# EvoProject_2_0.net
KiCad netlist of a schematic drawn in Altium Designer
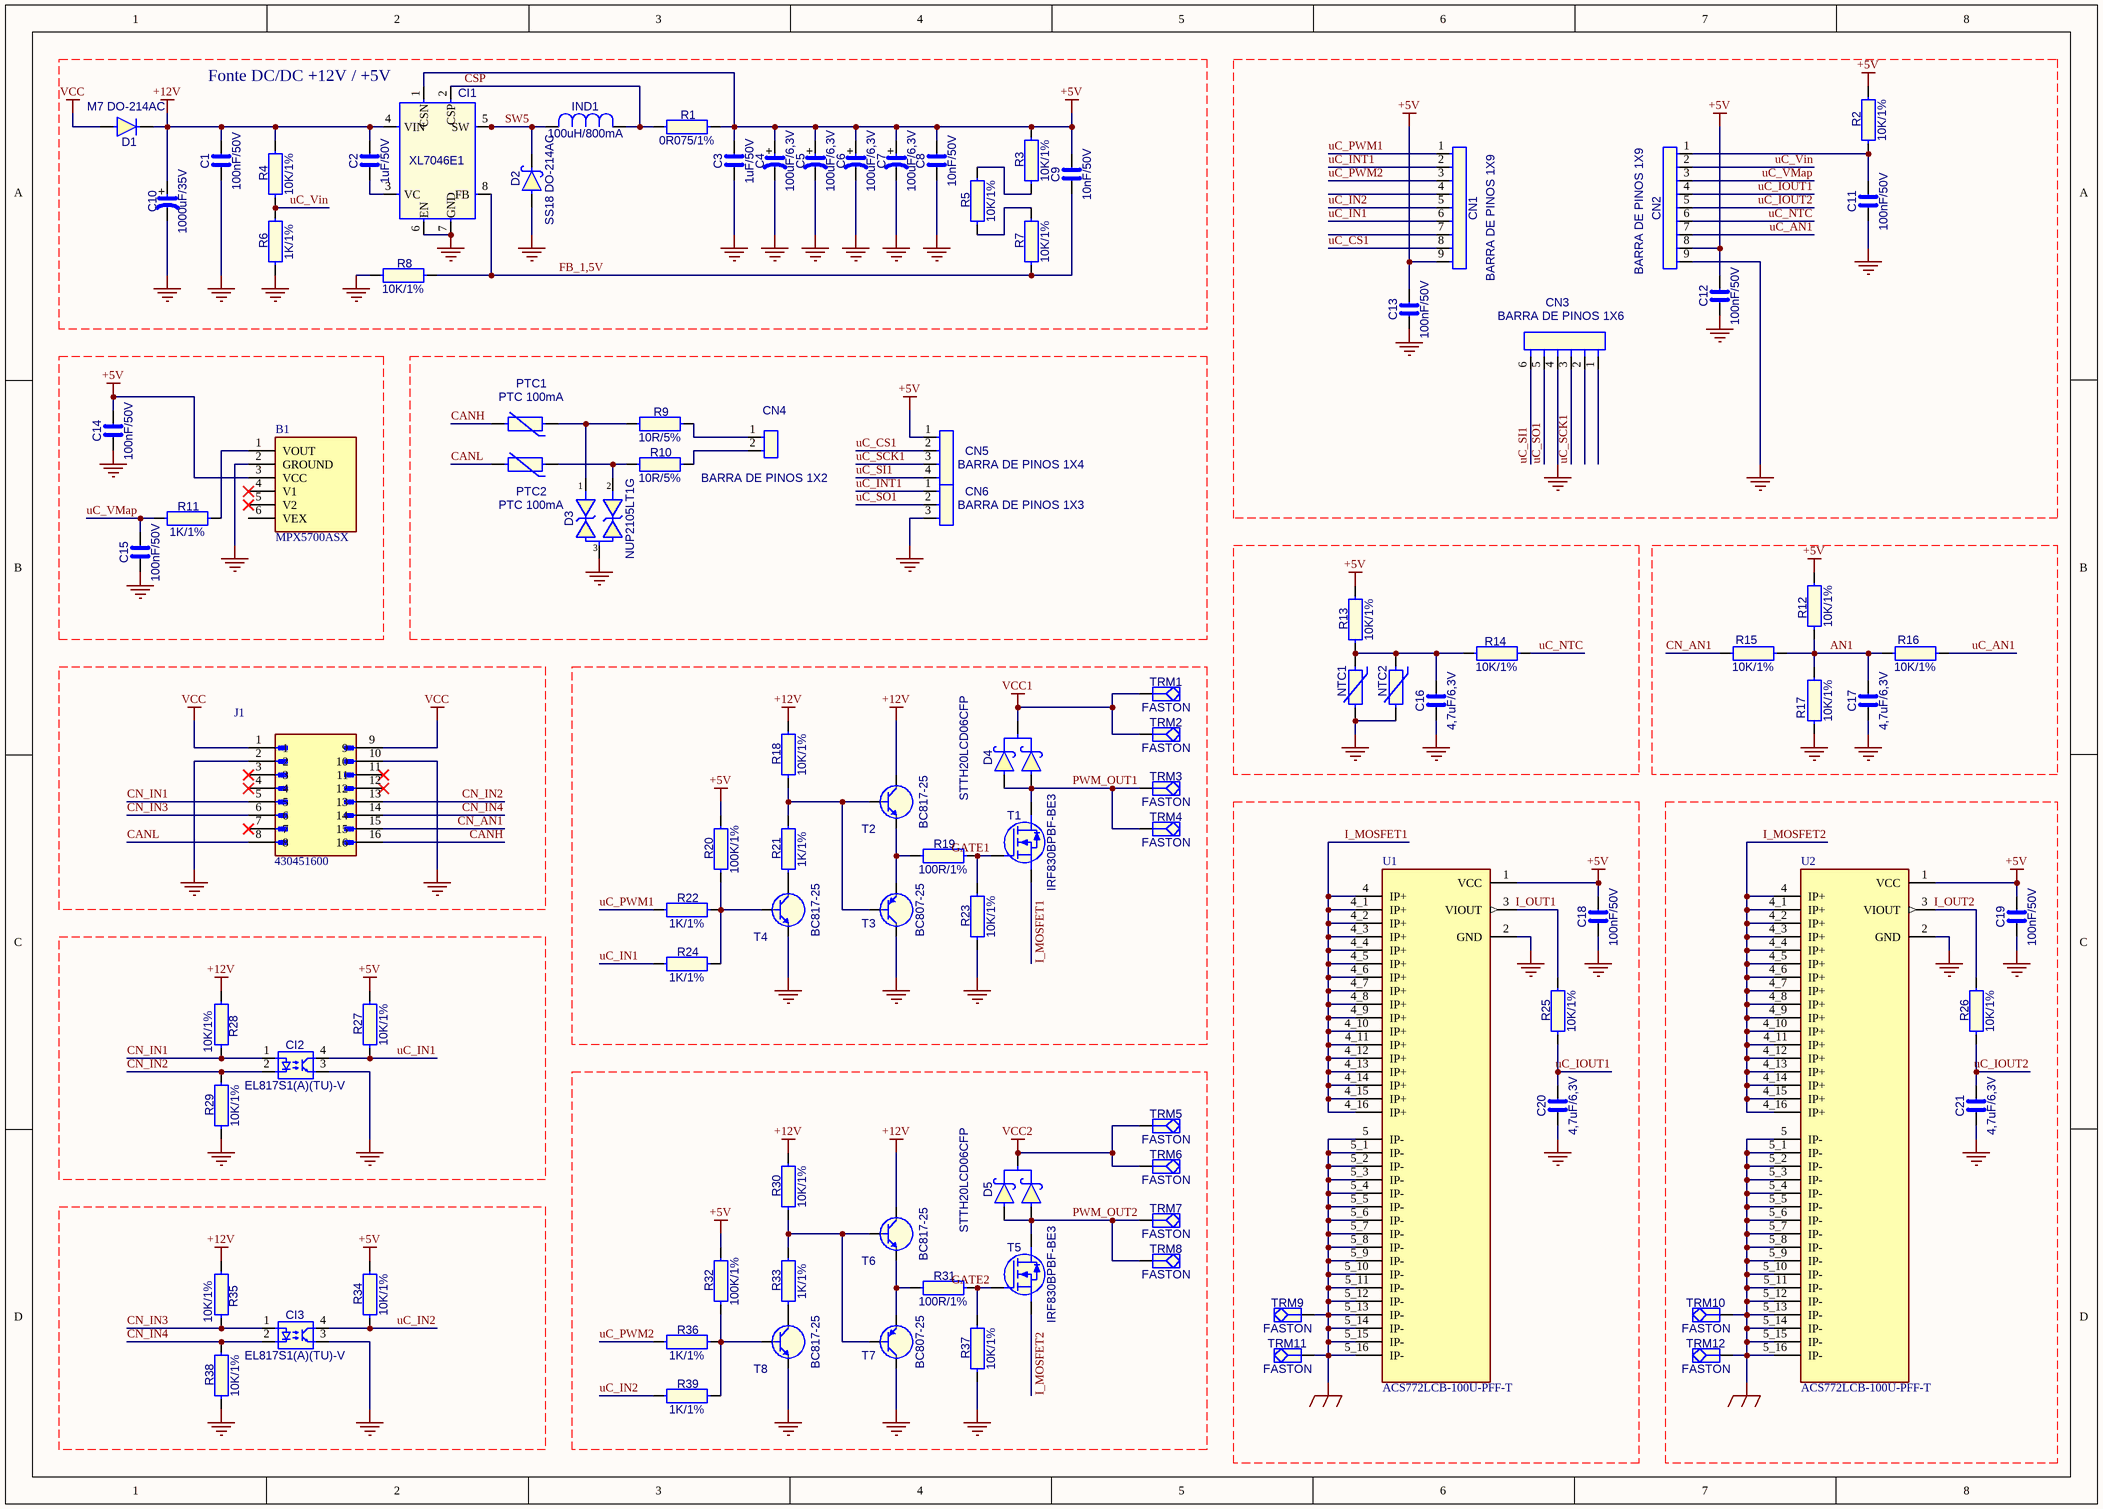
[diagram p0: EvoProject 2.0.SchDoc]

(export (version "E")
  (design (tool "Eeschema 10.0.6"))
  (components
    (comp (ref "B1")
      (value "MPX5700ASX")
      (footprint "MPX5700ASX")
      (libsource (lib "Inova_2015") (part "MPX5700ASX"))
    )
    (comp (ref "C1")
      (value "100nF/50V")
      (footprint "CAP SMD CE 0603 HR")
      (description "CAPACITOR SMD CE 0603 100nF 50V 10% X7R")
      (libsource (lib "INOVA SISTEMAS ELETRONICOS") (part "CAP_NP"))
    )
    (comp (ref "C2")
      (value "1uF/50V")
      (footprint "CAP SMD CE 0603 HR")
      (description "CAPACITOR SMD CE 0603 1uF 50V 10% X5R")
      (libsource (lib "INOVA SISTEMAS ELETRONICOS") (part "CAP_NP"))
    )
    (comp (ref "C3")
      (value "1uF/50V")
      (footprint "CAP SMD CE 0603 HR")
      (description "CAPACITOR SMD CE 0603 1uF 50V 10% X5R")
      (libsource (lib "INOVA SISTEMAS ELETRONICOS") (part "CAP_NP"))
    )
    (comp (ref "C4")
      (value "100uF/6,3V")
      (footprint "CAP SMD EL D.6,30 H.5,40 P.4,80 HR")
      (description "CAPACITOR SMD EL D.6.3 H.5.4mm 100uF 6.3V 20% BESR")
      (libsource (lib "INOVA SISTEMAS ELETRONICOS") (part "CAP_P"))
    )
    (comp (ref "C5")
      (value "100uF/6,3V")
      (footprint "CAP SMD EL D.6,30 H.5,40 P.4,80 HR")
      (description "CAPACITOR SMD EL D.6.3 H.5.4mm 100uF 6.3V 20% BESR")
      (libsource (lib "INOVA SISTEMAS ELETRONICOS") (part "CAP_P"))
    )
    (comp (ref "C6")
      (value "100uF/6,3V")
      (footprint "CAP SMD EL D.6,30 H.5,40 P.4,80 HR")
      (description "CAPACITOR SMD EL D.6.3 H.5.4mm 100uF 6.3V 20% BESR")
      (libsource (lib "INOVA SISTEMAS ELETRONICOS") (part "CAP_P"))
    )
    (comp (ref "C7")
      (value "100uF/6,3V")
      (footprint "CAP SMD EL D.6,30 H.5,40 P.4,80 HR")
      (description "CAPACITOR SMD EL D.6.3 H.5.4mm 100uF 6.3V 20% BESR")
      (libsource (lib "INOVA SISTEMAS ELETRONICOS") (part "CAP_P"))
    )
    (comp (ref "C8")
      (value "10nF/50V")
      (footprint "CAP SMD CE 0603 HR")
      (description "CAPACITOR SMD CE 0603 10nF 50V 20% X7R")
      (libsource (lib "INOVA SISTEMAS ELETRONICOS") (part "CAP_NP"))
    )
    (comp (ref "C9")
      (value "10nF/50V")
      (footprint "CAP SMD CE 0603 HR")
      (description "CAPACITOR SMD CE 0603 10nF 50V 20% X7R")
      (libsource (lib "INOVA SISTEMAS ELETRONICOS") (part "CAP_NP"))
    )
    (comp (ref "C10")
      (value "1000uF/35V")
      (footprint "CAP PTH EL D.13,00 H.20,00 P.5,00 RD MW")
      (description "CAPACITOR PTH EL 1000/35 20%")
      (libsource (lib "INOVA SISTEMAS ELETRONICOS") (part "CAP_P"))
    )
    (comp (ref "C11")
      (value "100nF/50V")
      (footprint "CAP SMD CE 0603 HR")
      (description "CAPACITOR SMD CE 0603 100nF 50V 10% X7R")
      (libsource (lib "INOVA SISTEMAS ELETRONICOS") (part "CAP_NP"))
    )
    (comp (ref "C12")
      (value "100nF/50V")
      (footprint "CAP SMD CE 0603 HR")
      (description "CAPACITOR SMD CE 0603 100nF 50V 10% X7R")
      (libsource (lib "INOVA SISTEMAS ELETRONICOS") (part "CAP_NP"))
    )
    (comp (ref "C13")
      (value "100nF/50V")
      (footprint "CAP SMD CE 0603 HR")
      (description "CAPACITOR SMD CE 0603 100nF 50V 10% X7R")
      (libsource (lib "INOVA SISTEMAS ELETRONICOS") (part "CAP_NP"))
    )
    (comp (ref "C14")
      (value "100nF/50V")
      (footprint "CAP SMD CE 0603 HR")
      (description "CAPACITOR SMD CE 0603 100nF 50V 10% X7R")
      (libsource (lib "INOVA SISTEMAS ELETRONICOS") (part "CAP_NP"))
    )
    (comp (ref "C15")
      (value "100nF/50V")
      (footprint "CAP SMD CE 0603 HR")
      (description "CAPACITOR SMD CE 0603 100nF 50V 10% X7R")
      (libsource (lib "INOVA SISTEMAS ELETRONICOS") (part "CAP_NP"))
    )
    (comp (ref "C16")
      (value "4,7uF/6,3V")
      (footprint "CAP SMD CE 0603 HR")
      (description "CAPACITOR SMD CE 0603 4,7uF 6.3V 10% X5R")
      (libsource (lib "INOVA SISTEMAS ELETRONICOS") (part "CAP_NP"))
    )
    (comp (ref "C17")
      (value "4,7uF/6,3V")
      (footprint "CAP SMD CE 0603 HR")
      (description "CAPACITOR SMD CE 0603 4,7uF 6.3V 10% X5R")
      (libsource (lib "INOVA SISTEMAS ELETRONICOS") (part "CAP_NP"))
    )
    (comp (ref "C18")
      (value "100nF/50V")
      (footprint "CAP SMD CE 0603 HR")
      (description "CAPACITOR SMD CE 0603 100nF 50V 10% X7R")
      (libsource (lib "INOVA SISTEMAS ELETRONICOS") (part "CAP_NP"))
    )
    (comp (ref "C19")
      (value "100nF/50V")
      (footprint "CAP SMD CE 0603 HR")
      (description "CAPACITOR SMD CE 0603 100nF 50V 10% X7R")
      (libsource (lib "INOVA SISTEMAS ELETRONICOS") (part "CAP_NP"))
    )
    (comp (ref "C20")
      (value "4,7uF/6,3V")
      (footprint "CAP SMD CE 0603 HR")
      (description "CAPACITOR SMD CE 0603 4,7uF 6.3V 10% X5R")
      (libsource (lib "INOVA SISTEMAS ELETRONICOS") (part "CAP_NP"))
    )
    (comp (ref "C21")
      (value "4,7uF/6,3V")
      (footprint "CAP SMD CE 0603 HR")
      (description "CAPACITOR SMD CE 0603 4,7uF 6.3V 10% X5R")
      (libsource (lib "INOVA SISTEMAS ELETRONICOS") (part "CAP_NP"))
    )
    (comp (ref "CI1")
      (value "XL7046E1")
      (footprint "GEN SMD SOIC8 TP P.1,27 MR")
      (description "CI SMD REBAIXADOR DE TENSÃO XL7046E1")
      (libsource (lib "INOVA SISTEMAS ELETRONICOS") (part "CI_XL7046"))
    )
    (comp (ref "CI2")
      (value "EL817S1(A)(TU)-V")
      (footprint "GEN SMD SOIC4 P.1,27 MR")
      (description "CI OPTOACOPLADOR SMD DIP-4 1CH 817 70V 80~160%")
      (libsource (lib "INOVA SISTEMAS ELETRONICOS") (part "OPT_4 pinos"))
    )
    (comp (ref "CI3")
      (value "EL817S1(A)(TU)-V")
      (footprint "GEN SMD SOIC4 P.1,27 MR")
      (description "CI OPTOACOPLADOR SMD DIP-4 1CH 817 70V 80~160%")
      (libsource (lib "INOVA SISTEMAS ELETRONICOS") (part "OPT_4 pinos"))
    )
    (comp (ref "CN1")
      (value "BARRA DE PINOS 1X9")
      (footprint "CON PTH BAR P.2,54 1x9 180D MW")
      (description "BARRA DE PINOS 180° RETOS (CORTAR 9 PINOS)")
      (libsource (lib "") (part "CON_9 Vias Simples_1"))
    )
    (comp (ref "CN2")
      (value "BARRA DE PINOS 1X9")
      (footprint "CON PTH BAR P.2,54 1x9 180D MW")
      (description "BARRA DE PINOS 180° RETOS (CORTAR 9 PINOS)")
      (libsource (lib "INOVA SISTEMAS ELETRONICOS") (part "CON_9 Vias Simples"))
    )
    (comp (ref "CN3")
      (value "BARRA DE PINOS 1X6")
      (footprint "CON PTH BAR  W. L. H. P.2,54mm 1x6 180D MW")
      (description "CONECTOR BARRA DE PINOS 180° 1X6")
      (libsource (lib "INOVA SISTEMAS ELETRONICOS") (part "CON_6 Vias Simples"))
    )
    (comp (ref "CN4")
      (value "BARRA DE PINOS 1X2")
      (footprint "CON PTH BAR  W. L. H. P.02,54mm 1x2 180D MW")
      (description "BARRA DE PINOS 180° RETOS (CORTAR 2 PINOS)")
      (libsource (lib "INOVA SISTEMAS ELETRONICOS") (part "CON_2 Vias Simples"))
    )
    (comp (ref "CN5")
      (value "BARRA DE PINOS 1X4")
      (footprint "CON PTH BAR  W. L. H. P.02,54mm 1x4 180D MW")
      (description "BARRA DE PINOS 180° RETOS (CORTAR 4 PINOS)")
      (libsource (lib "INOVA SISTEMAS ELETRONICOS") (part "CON_4 Vias Simples"))
    )
    (comp (ref "CN6")
      (value "BARRA DE PINOS 1X3")
      (footprint "CON PTH BAR  W. L. H. P.2,54mm 1x3 180D MW")
      (description "BARRA DE PINOS 180° RETOS (CORTAR 3 PINOS)")
      (libsource (lib "INOVA SISTEMAS ELETRONICOS") (part "CON_3 Vias Simples"))
    )
    (comp (ref "D1")
      (value "M7 DO-214AC")
      (footprint "DIO SMD SMA DO214AC MR")
      (description "DIODO SMD 1N4007 SMA")
      (libsource (lib "INOVA SISTEMAS ELETRONICOS") (part "DIO_Comum"))
    )
    (comp (ref "D2")
      (value "SS18 DO-214AC")
      (footprint "DIO SMD SMA DO214AC HR")
      (description "DIODO SMD SS18 1A 80V SCHOTTKY")
      (libsource (lib "INOVA SISTEMAS ELETRONICOS") (part "DIO_Schottky"))
    )
    (comp (ref "D3")
      (value "NUP2105LT1G")
      (footprint "GEN SMD SOT23-3 TO-236AA MR")
      (description "DIODO SMD TVS SOT23 24V 50A 350W")
      (libsource (lib "INOVA SISTEMAS ELETRONICOS") (part "DIO_NUP2105L"))
    )
    (comp (ref "D4")
      (value "STTH20LCD06CFP")
      (footprint "GEN PTH TO-220AB P.2,54 LW")
      (description "DIODO PTH STTH20LCD06CFP ULTRAFAST (PF07-6.5-V)")
      (libsource (lib "INOVA SISTEMAS ELETRONICOS") (part "DIO_Schottky Duplo"))
    )
    (comp (ref "D5")
      (value "STTH20LCD06CFP")
      (footprint "GEN PTH TO-220AB P.2,54 LW")
      (description "DIODO PTH STTH20LCD06CFP ULTRAFAST (PF07-6.5-V)")
      (libsource (lib "INOVA SISTEMAS ELETRONICOS") (part "DIO_Schottky Duplo"))
    )
    (comp (ref "IND1")
      (value "100uH/800mA")
      (footprint "IND SMD L.6,30 P.4,82 MR")
      (description "INDUTOR SMD 100uH 800mA")
      (libsource (lib "INOVA SISTEMAS ELETRONICOS") (part "IND_2 Terminais"))
    )
    (comp (ref "J1")
      (value "430451600")
      (footprint "MOLEX_430451600")
      (description "Conn Wire to Board HDR 16 POS 3mm Solder RA Side Entry Thru-Hole Micro-Fit 3.0â„¢ Tray")
      (fields (field (name "MF") "Molex"))
      (libsource (lib "430451600") (part "430451600"))
    )
    (comp (ref "NTC1")
      (value "MF52A103H3950(A2)")
      (footprint "RES PTH NTC RADIAL P.2,54 LW")
      (description "TERMISTOR NTC 10K (PF)")
      (libsource (lib "INOVA SISTEMAS ELETRONICOS") (part "RES_NTC"))
    )
    (comp (ref "NTC2")
      (value "NTC 10k")
      (footprint "RES SMD CH 0805 HR")
      (description "TERMISTOR SMD NTC 0805 10K BETA 3970 3%")
      (libsource (lib "INOVA SISTEMAS ELETRONICOS") (part "RES_NTC"))
    )
    (comp (ref "PTC1")
      (value "PTC 100mA")
      (footprint "PTC SMD CH 0805 HR")
      (description "TERMISTOR SMD PTC 0805 0,1A 24V NHC")
      (libsource (lib "INOVA SISTEMAS ELETRONICOS") (part "RES_PTC"))
    )
    (comp (ref "PTC2")
      (value "PTC 100mA")
      (footprint "PTC SMD CH 0805 HR")
      (description "TERMISTOR SMD PTC 0805 0,1A 24V NHC")
      (libsource (lib "INOVA SISTEMAS ELETRONICOS") (part "RES_PTC"))
    )
    (comp (ref "R1")
      (value "0R075/1%")
      (footprint "RES SMD CH 1206 HR")
      (description "RESISTOR SMD CH 1206 0R075 1% 1/4W")
      (libsource (lib "INOVA SISTEMAS ELETRONICOS") (part "RES_Geral"))
    )
    (comp (ref "R2")
      (value "10K/1%")
      (footprint "RES SMD CH 0603 HR")
      (description "RESISTOR SMD CH 0603 10K 1% 1/10W")
      (libsource (lib "") (part "RES_Geral_1"))
    )
    (comp (ref "R3")
      (value "10K/1%")
      (footprint "RES SMD CH 0603 HR")
      (description "RESISTOR SMD CH 0603 10K 1% 1/10W")
      (libsource (lib "") (part "RES_Geral_1"))
    )
    (comp (ref "R4")
      (value "10K/1%")
      (footprint "RES SMD CH 0603 HR")
      (description "RESISTOR SMD CH 0603 10K 1% 1/10W")
      (libsource (lib "") (part "RES_Geral_1"))
    )
    (comp (ref "R5")
      (value "10K/1%")
      (footprint "RES SMD CH 0603 HR")
      (description "RESISTOR SMD CH 0603 10K 1% 1/10W")
      (libsource (lib "") (part "RES_Geral_1"))
    )
    (comp (ref "R6")
      (value "1K/1%")
      (footprint "RES SMD CH 0603 HR")
      (description "RESISTOR SMD CH 0603 1K 1% 1/10W")
      (libsource (lib "") (part "RES_Geral_1"))
    )
    (comp (ref "R7")
      (value "10K/1%")
      (footprint "RES SMD CH 0603 HR")
      (description "RESISTOR SMD CH 0603 10K 1% 1/10W")
      (libsource (lib "") (part "RES_Geral_1"))
    )
    (comp (ref "R8")
      (value "10K/1%")
      (footprint "RES SMD CH 0603 HR")
      (description "RESISTOR SMD CH 0603 10K 1% 1/10W")
      (libsource (lib "INOVA SISTEMAS ELETRONICOS") (part "RES_Geral"))
    )
    (comp (ref "R9")
      (value "10R/5%")
      (footprint "RES SMD CH 0603 HR")
      (description "RESISTOR SMD CH 0603 10R 5% 1/10W")
      (libsource (lib "INOVA SISTEMAS ELETRONICOS") (part "RES_Geral"))
    )
    (comp (ref "R10")
      (value "10R/5%")
      (footprint "RES SMD CH 0603 HR")
      (description "RESISTOR SMD CH 0603 10R 5% 1/10W")
      (libsource (lib "INOVA SISTEMAS ELETRONICOS") (part "RES_Geral"))
    )
    (comp (ref "R11")
      (value "1K/1%")
      (footprint "RES SMD CH 0603 HR")
      (description "RESISTOR SMD CH 0603 1K 1% 1/10W")
      (libsource (lib "INOVA SISTEMAS ELETRONICOS") (part "RES_Geral"))
    )
    (comp (ref "R12")
      (value "10K/1%")
      (footprint "RES SMD CH 0603 HR")
      (description "RESISTOR SMD CH 0603 10K 1% 1/10W")
      (libsource (lib "") (part "RES_Geral_3"))
    )
    (comp (ref "R13")
      (value "10K/1%")
      (footprint "RES SMD CH 0603 HR")
      (description "RESISTOR SMD CH 0603 10K 1% 1/10W")
      (libsource (lib "") (part "RES_Geral_1"))
    )
    (comp (ref "R14")
      (value "10K/1%")
      (footprint "RES SMD CH 0603 HR")
      (description "RESISTOR SMD CH 0603 10K 1% 1/10W")
      (libsource (lib "") (part "RES_Geral_2"))
    )
    (comp (ref "R15")
      (value "10K/1%")
      (footprint "RES SMD CH 0603 HR")
      (description "RESISTOR SMD CH 0603 10K 1% 1/10W")
      (libsource (lib "") (part "RES_Geral_2"))
    )
    (comp (ref "R16")
      (value "10K/1%")
      (footprint "RES SMD CH 0603 HR")
      (description "RESISTOR SMD CH 0603 10K 1% 1/10W")
      (libsource (lib "") (part "RES_Geral_2"))
    )
    (comp (ref "R17")
      (value "10K/1%")
      (footprint "RES SMD CH 0603 HR")
      (description "RESISTOR SMD CH 0603 10K 1% 1/10W")
      (libsource (lib "") (part "RES_Geral_3"))
    )
    (comp (ref "R18")
      (value "10K/1%")
      (footprint "RES SMD CH 0603 HR")
      (description "RESISTOR SMD CH 0603 10K 1% 1/10W")
      (libsource (lib "") (part "RES_Geral_1"))
    )
    (comp (ref "R19")
      (value "100R/1%")
      (footprint "RES SMD CH 0603 HR")
      (description "RESISTOR SMD CH 0603 100R 1% 1/10W")
      (libsource (lib "INOVA SISTEMAS ELETRONICOS") (part "RES_Geral"))
    )
    (comp (ref "R20")
      (value "100K/1%")
      (footprint "RES SMD CH 0603 HR")
      (description "RESISTOR SMD CH 0603 100K 1% 1/10W")
      (libsource (lib "") (part "RES_Geral_1"))
    )
    (comp (ref "R21")
      (value "1K/1%")
      (footprint "RES SMD CH 0603 HR")
      (description "RESISTOR SMD CH 0603 1K 1% 1/10W")
      (libsource (lib "") (part "RES_Geral_1"))
    )
    (comp (ref "R22")
      (value "1K/1%")
      (footprint "RES SMD CH 0603 HR")
      (description "RESISTOR SMD CH 0603 1K 1% 1/10W")
      (libsource (lib "INOVA SISTEMAS ELETRONICOS") (part "RES_Geral"))
    )
    (comp (ref "R23")
      (value "10K/1%")
      (footprint "RES SMD CH 0603 HR")
      (description "RESISTOR SMD CH 0603 10K 1% 1/10W")
      (libsource (lib "") (part "RES_Geral_1"))
    )
    (comp (ref "R24")
      (value "1K/1%")
      (footprint "RES SMD CH 0603 HR")
      (description "RESISTOR SMD CH 0603 1K 1% 1/10W")
      (libsource (lib "INOVA SISTEMAS ELETRONICOS") (part "RES_Geral"))
    )
    (comp (ref "R25")
      (value "10K/1%")
      (footprint "RES SMD CH 0603 HR")
      (description "RESISTOR SMD CH 0603 10K 1% 1/10W")
      (libsource (lib "") (part "RES_Geral_1"))
    )
    (comp (ref "R26")
      (value "10K/1%")
      (footprint "RES SMD CH 0603 HR")
      (description "RESISTOR SMD CH 0603 10K 1% 1/10W")
      (libsource (lib "") (part "RES_Geral_1"))
    )
    (comp (ref "R27")
      (value "10K/1%")
      (footprint "RES SMD CH 0603 HR")
      (description "RESISTOR SMD CH 0603 10K 1% 1/10W")
      (libsource (lib "") (part "RES_Geral_1"))
    )
    (comp (ref "R28")
      (value "10K/1%")
      (footprint "RES SMD CH 0603 HR")
      (description "RESISTOR SMD CH 0603 10K 1% 1/10W")
      (libsource (lib "") (part "RES_Geral_2"))
    )
    (comp (ref "R29")
      (value "10K/1%")
      (footprint "RES SMD CH 0603 HR")
      (description "RESISTOR SMD CH 0603 10K 1% 1/10W")
      (libsource (lib "") (part "RES_Geral_1"))
    )
    (comp (ref "R30")
      (value "10K/1%")
      (footprint "RES SMD CH 0603 HR")
      (description "RESISTOR SMD CH 0603 10K 1% 1/10W")
      (libsource (lib "") (part "RES_Geral_1"))
    )
    (comp (ref "R31")
      (value "100R/1%")
      (footprint "RES SMD CH 0603 HR")
      (description "RESISTOR SMD CH 0603 100R 1% 1/10W")
      (libsource (lib "INOVA SISTEMAS ELETRONICOS") (part "RES_Geral"))
    )
    (comp (ref "R32")
      (value "100K/1%")
      (footprint "RES SMD CH 0603 HR")
      (description "RESISTOR SMD CH 0603 100K 1% 1/10W")
      (libsource (lib "") (part "RES_Geral_1"))
    )
    (comp (ref "R33")
      (value "1K/1%")
      (footprint "RES SMD CH 0603 HR")
      (description "RESISTOR SMD CH 0603 1K 1% 1/10W")
      (libsource (lib "") (part "RES_Geral_1"))
    )
    (comp (ref "R34")
      (value "10K/1%")
      (footprint "RES SMD CH 0603 HR")
      (description "RESISTOR SMD CH 0603 10K 1% 1/10W")
      (libsource (lib "") (part "RES_Geral_1"))
    )
    (comp (ref "R35")
      (value "10K/1%")
      (footprint "RES SMD CH 0603 HR")
      (description "RESISTOR SMD CH 0603 10K 1% 1/10W")
      (libsource (lib "") (part "RES_Geral_2"))
    )
    (comp (ref "R36")
      (value "1K/1%")
      (footprint "RES SMD CH 0603 HR")
      (description "RESISTOR SMD CH 0603 1K 1% 1/10W")
      (libsource (lib "INOVA SISTEMAS ELETRONICOS") (part "RES_Geral"))
    )
    (comp (ref "R37")
      (value "10K/1%")
      (footprint "RES SMD CH 0603 HR")
      (description "RESISTOR SMD CH 0603 10K 1% 1/10W")
      (libsource (lib "") (part "RES_Geral_1"))
    )
    (comp (ref "R38")
      (value "10K/1%")
      (footprint "RES SMD CH 0603 HR")
      (description "RESISTOR SMD CH 0603 10K 1% 1/10W")
      (libsource (lib "") (part "RES_Geral_1"))
    )
    (comp (ref "R39")
      (value "1K/1%")
      (footprint "RES SMD CH 0603 HR")
      (description "RESISTOR SMD CH 0603 1K 1% 1/10W")
      (libsource (lib "INOVA SISTEMAS ELETRONICOS") (part "RES_Geral"))
    )
    (comp (ref "T1")
      (value "IRF830BPBF-BE3")
      (footprint "GEN PTH TO-220AB P.2,54 LW")
      (description "TRANSISTOR PTH MOSFET IRF830BPBF-BE3 500V, 5,5A @ 25C°")
      (libsource (lib "INOVA SISTEMAS ELETRONICOS") (part "TRA_MOSFET_N-DPAK TO-252-3 TO-220AB"))
    )
    (comp (ref "T2")
      (value "BC817-25")
      (footprint "GEN SMD SOT23-3 TO-236AA MR")
      (description "TRANSISTOR SMD 817/25")
      (libsource (lib "INOVA SISTEMAS ELETRONICOS") (part "TRA_NPN SOT-23-3L"))
    )
    (comp (ref "T3")
      (value "BC807-25")
      (footprint "GEN SMD SOT23-3 TO-236AA MR")
      (description "TRANSISTOR SMD 807/25")
      (libsource (lib "INOVA SISTEMAS ELETRONICOS") (part "TRA_PNP SOT-23-3L"))
    )
    (comp (ref "T4")
      (value "BC817-25")
      (footprint "GEN SMD SOT23-3 TO-236AA MR")
      (description "TRANSISTOR SMD 817/25")
      (libsource (lib "INOVA SISTEMAS ELETRONICOS") (part "TRA_NPN SOT-23-3L"))
    )
    (comp (ref "T5")
      (value "IRF830BPBF-BE3")
      (footprint "GEN PTH TO-220AB P.2,54 LW")
      (description "TRANSISTOR PTH MOSFET IRF830BPBF-BE3 500V, 5,5A @ 25C°")
      (libsource (lib "INOVA SISTEMAS ELETRONICOS") (part "TRA_MOSFET_N-DPAK TO-252-3 TO-220AB"))
    )
    (comp (ref "T6")
      (value "BC817-25")
      (footprint "GEN SMD SOT23-3 TO-236AA MR")
      (description "TRANSISTOR SMD 817/25")
      (libsource (lib "INOVA SISTEMAS ELETRONICOS") (part "TRA_NPN SOT-23-3L"))
    )
    (comp (ref "T7")
      (value "BC807-25")
      (footprint "GEN SMD SOT23-3 TO-236AA MR")
      (description "TRANSISTOR SMD 807/25")
      (libsource (lib "INOVA SISTEMAS ELETRONICOS") (part "TRA_PNP SOT-23-3L"))
    )
    (comp (ref "T8")
      (value "BC817-25")
      (footprint "GEN SMD SOT23-3 TO-236AA MR")
      (description "TRANSISTOR SMD 817/25")
      (libsource (lib "INOVA SISTEMAS ELETRONICOS") (part "TRA_NPN SOT-23-3L"))
    )
    (comp (ref "TRM1")
      (value "FASTON")
      (footprint "Terminal Faston Macho 180° OBLONGO COM SUPORTE")
      (description "TERMINAL P/ PCI 180° 6,35mmX14,2mm BAIONETA")
      (libsource (lib "INOVA SISTEMAS ELETRONICOS") (part "CON_TERMINAL"))
    )
    (comp (ref "TRM2")
      (value "FASTON")
      (footprint "Terminal Faston Macho 180° OBLONGO COM SUPORTE")
      (description "TERMINAL P/ PCI 180° 6,35mmX14,2mm BAIONETA")
      (libsource (lib "INOVA SISTEMAS ELETRONICOS") (part "CON_TERMINAL"))
    )
    (comp (ref "TRM3")
      (value "FASTON")
      (footprint "Terminal Faston Macho 180° OBLONGO COM SUPORTE")
      (description "TERMINAL P/ PCI 180° 6,35mmX14,2mm BAIONETA")
      (libsource (lib "INOVA SISTEMAS ELETRONICOS") (part "CON_TERMINAL"))
    )
    (comp (ref "TRM4")
      (value "FASTON")
      (footprint "Terminal Faston Macho 180° OBLONGO COM SUPORTE")
      (description "TERMINAL P/ PCI 180° 6,35mmX14,2mm BAIONETA")
      (libsource (lib "INOVA SISTEMAS ELETRONICOS") (part "CON_TERMINAL"))
    )
    (comp (ref "TRM5")
      (value "FASTON")
      (footprint "Terminal Faston Macho 180° OBLONGO COM SUPORTE")
      (description "TERMINAL P/ PCI 180° 6,35mmX14,2mm BAIONETA")
      (libsource (lib "INOVA SISTEMAS ELETRONICOS") (part "CON_TERMINAL"))
    )
    (comp (ref "TRM6")
      (value "FASTON")
      (footprint "Terminal Faston Macho 180° OBLONGO COM SUPORTE")
      (description "TERMINAL P/ PCI 180° 6,35mmX14,2mm BAIONETA")
      (libsource (lib "INOVA SISTEMAS ELETRONICOS") (part "CON_TERMINAL"))
    )
    (comp (ref "TRM7")
      (value "FASTON")
      (footprint "Terminal Faston Macho 180° OBLONGO COM SUPORTE")
      (description "TERMINAL P/ PCI 180° 6,35mmX14,2mm BAIONETA")
      (libsource (lib "INOVA SISTEMAS ELETRONICOS") (part "CON_TERMINAL"))
    )
    (comp (ref "TRM8")
      (value "FASTON")
      (footprint "Terminal Faston Macho 180° OBLONGO COM SUPORTE")
      (description "TERMINAL P/ PCI 180° 6,35mmX14,2mm BAIONETA")
      (libsource (lib "INOVA SISTEMAS ELETRONICOS") (part "CON_TERMINAL"))
    )
    (comp (ref "TRM9")
      (value "FASTON")
      (footprint "Terminal Faston Macho 180° OBLONGO COM SUPORTE")
      (description "TERMINAL P/ PCI 180° 6,35mmX14,2mm BAIONETA")
      (libsource (lib "") (part "CON_TERMINAL_1"))
    )
    (comp (ref "TRM10")
      (value "FASTON")
      (footprint "Terminal Faston Macho 180° OBLONGO COM SUPORTE")
      (description "TERMINAL P/ PCI 180° 6,35mmX14,2mm BAIONETA")
      (libsource (lib "") (part "CON_TERMINAL_1"))
    )
    (comp (ref "TRM11")
      (value "FASTON")
      (footprint "Terminal Faston Macho 180° OBLONGO COM SUPORTE")
      (description "TERMINAL P/ PCI 180° 6,35mmX14,2mm BAIONETA")
      (libsource (lib "") (part "CON_TERMINAL_1"))
    )
    (comp (ref "TRM12")
      (value "FASTON")
      (footprint "Terminal Faston Macho 180° OBLONGO COM SUPORTE")
      (description "TERMINAL P/ PCI 180° 6,35mmX14,2mm BAIONETA")
      (libsource (lib "") (part "CON_TERMINAL_1"))
    )
    (comp (ref "U1")
      (value "ACS772LCB-100U-PFF-T")
      (footprint "XDCR_ACS772LCB-100U-PFF-T")
      (description "Current Sensor 100A 1 Channel Hall Effect Unidirectional 5-CB Formed Leads, PFF")
      (fields (field (name "MF") "Allegro MicroSystems LLC"))
      (libsource (lib "ACS772LCB-100U-PFF-T") (part "ACS772LCB-100U-PFF-T"))
    )
    (comp (ref "U2")
      (value "ACS772LCB-100U-PFF-T")
      (footprint "XDCR_ACS772LCB-100U-PFF-T")
      (description "Current Sensor 100A 1 Channel Hall Effect Unidirectional 5-CB Formed Leads, PFF")
      (fields (field (name "MF") "Allegro MicroSystems LLC"))
      (libsource (lib "ACS772LCB-100U-PFF-T") (part "ACS772LCB-100U-PFF-T"))
    )
  )
  (nets
    (net (code "1") (name "+5V") (class "Default")
      (node (ref "B1") (pin "3") (pinfunction "VCC_3") (pintype "passive"))
      (node (ref "C12") (pin "2") (pinfunction "2_2") (pintype "passive"))
      (node (ref "C13") (pin "2") (pinfunction "2_2") (pintype "passive"))
      (node (ref "C14") (pin "1") (pinfunction "1_1") (pintype "passive"))
      (node (ref "C18") (pin "1") (pinfunction "1_1") (pintype "passive"))
      (node (ref "C19") (pin "1") (pinfunction "1_1") (pintype "passive"))
      (node (ref "C3") (pin "1") (pinfunction "1_1") (pintype "passive"))
      (node (ref "C4") (pin "2") (pinfunction "Plus_2") (pintype "passive"))
      (node (ref "C5") (pin "2") (pinfunction "Plus_2") (pintype "passive"))
      (node (ref "C6") (pin "2") (pinfunction "Plus_2") (pintype "passive"))
      (node (ref "C7") (pin "2") (pinfunction "Plus_2") (pintype "passive"))
      (node (ref "C8") (pin "1") (pinfunction "1_1") (pintype "passive"))
      (node (ref "C9") (pin "1") (pinfunction "1_1") (pintype "passive"))
      (node (ref "CI1") (pin "1") (pinfunction "CSN_1") (pintype "passive"))
      (node (ref "CN1") (pin "9") (pinfunction "9_9") (pintype "passive"))
      (node (ref "CN2") (pin "8") (pinfunction "8_8") (pintype "passive"))
      (node (ref "CN5") (pin "1") (pinfunction "1_1") (pintype "passive"))
      (node (ref "R1") (pin "2") (pinfunction "2_2") (pintype "passive"))
      (node (ref "R12") (pin "1") (pinfunction "1_1") (pintype "passive"))
      (node (ref "R13") (pin "2") (pinfunction "2_2") (pintype "passive"))
      (node (ref "R2") (pin "2") (pinfunction "2_2") (pintype "passive"))
      (node (ref "R20") (pin "2") (pinfunction "2_2") (pintype "passive"))
      (node (ref "R27") (pin "2") (pinfunction "2_2") (pintype "passive"))
      (node (ref "R3") (pin "2") (pinfunction "2_2") (pintype "passive"))
      (node (ref "R32") (pin "2") (pinfunction "2_2") (pintype "passive"))
      (node (ref "R34") (pin "2") (pinfunction "2_2") (pintype "passive"))
      (node (ref "U1") (pin "1") (pinfunction "VCC_1") (pintype "power_in"))
      (node (ref "U2") (pin "1") (pinfunction "VCC_1") (pintype "power_in"))
    )
    (net (code "2") (name "+12V") (class "Default")
      (node (ref "C1") (pin "1") (pinfunction "1_1") (pintype "passive"))
      (node (ref "C10") (pin "2") (pinfunction "Plus_2") (pintype "passive"))
      (node (ref "C2") (pin "1") (pinfunction "1_1") (pintype "passive"))
      (node (ref "CI1") (pin "4") (pinfunction "VIN_4") (pintype "power_in"))
      (node (ref "D1") (pin "1") (pinfunction "K_1") (pintype "passive"))
      (node (ref "R18") (pin "2") (pinfunction "2_2") (pintype "passive"))
      (node (ref "R28") (pin "1") (pinfunction "1_1") (pintype "passive"))
      (node (ref "R30") (pin "2") (pinfunction "2_2") (pintype "passive"))
      (node (ref "R35") (pin "1") (pinfunction "1_1") (pintype "passive"))
      (node (ref "R4") (pin "2") (pinfunction "2_2") (pintype "passive"))
      (node (ref "T2") (pin "3") (pinfunction "C_3") (pintype "passive"))
      (node (ref "T6") (pin "3") (pinfunction "C_3") (pintype "passive"))
    )
    (net (code "3") (name "/AN1") (class "Default")
      (node (ref "C17") (pin "1") (pinfunction "1_1") (pintype "passive"))
      (node (ref "R12") (pin "2") (pinfunction "2_2") (pintype "passive"))
      (node (ref "R15") (pin "1") (pinfunction "1_1") (pintype "passive"))
      (node (ref "R16") (pin "2") (pinfunction "2_2") (pintype "passive"))
      (node (ref "R17") (pin "1") (pinfunction "1_1") (pintype "passive"))
    )
    (net (code "4") (name "/CANH") (class "Default")
      (node (ref "J1") (pin "16") (pinfunction "16_16") (pintype "passive"))
      (node (ref "PTC1") (pin "1") (pinfunction "1_1") (pintype "passive"))
    )
    (net (code "5") (name "/CANL") (class "Default")
      (node (ref "J1") (pin "8") (pinfunction "8_8") (pintype "passive"))
      (node (ref "PTC2") (pin "1") (pinfunction "1_1") (pintype "passive"))
    )
    (net (code "6") (name "/CN_AN1") (class "Default")
      (node (ref "J1") (pin "15") (pinfunction "15_15") (pintype "passive"))
      (node (ref "R15") (pin "2") (pinfunction "2_2") (pintype "passive"))
    )
    (net (code "7") (name "/CN_IN1") (class "Default")
      (node (ref "CI2") (pin "1") (pinfunction "A_1") (pintype "passive"))
      (node (ref "J1") (pin "5") (pinfunction "5_5") (pintype "passive"))
      (node (ref "R28") (pin "2") (pinfunction "2_2") (pintype "passive"))
    )
    (net (code "8") (name "/CN_IN2") (class "Default")
      (node (ref "CI2") (pin "2") (pinfunction "K_2") (pintype "passive"))
      (node (ref "J1") (pin "13") (pinfunction "13_13") (pintype "passive"))
      (node (ref "R29") (pin "2") (pinfunction "2_2") (pintype "passive"))
    )
    (net (code "9") (name "/CN_IN3") (class "Default")
      (node (ref "CI3") (pin "1") (pinfunction "A_1") (pintype "passive"))
      (node (ref "J1") (pin "6") (pinfunction "6_6") (pintype "passive"))
      (node (ref "R35") (pin "2") (pinfunction "2_2") (pintype "passive"))
    )
    (net (code "10") (name "/CN_IN4") (class "Default")
      (node (ref "CI3") (pin "2") (pinfunction "K_2") (pintype "passive"))
      (node (ref "J1") (pin "14") (pinfunction "14_14") (pintype "passive"))
      (node (ref "R38") (pin "2") (pinfunction "2_2") (pintype "passive"))
    )
    (net (code "11") (name "/CSP") (class "Default")
      (node (ref "CI1") (pin "2") (pinfunction "CSP_2") (pintype "passive"))
      (node (ref "IND1") (pin "2") (pinfunction "2_2") (pintype "passive"))
      (node (ref "R1") (pin "1") (pinfunction "1_1") (pintype "passive"))
    )
    (net (code "12") (name "/FB_1,5V") (class "Default")
      (node (ref "C9") (pin "2") (pinfunction "2_2") (pintype "passive"))
      (node (ref "CI1") (pin "8") (pinfunction "FB_8") (pintype "passive"))
      (node (ref "R7") (pin "1") (pinfunction "1_1") (pintype "passive"))
      (node (ref "R8") (pin "2") (pinfunction "2_2") (pintype "passive"))
    )
    (net (code "13") (name "/GATE1") (class "Default")
      (node (ref "R19") (pin "2") (pinfunction "2_2") (pintype "passive"))
      (node (ref "R23") (pin "2") (pinfunction "2_2") (pintype "passive"))
      (node (ref "T1") (pin "1") (pinfunction "G_1") (pintype "passive"))
    )
    (net (code "14") (name "/GATE2") (class "Default")
      (node (ref "R31") (pin "2") (pinfunction "2_2") (pintype "passive"))
      (node (ref "R37") (pin "2") (pinfunction "2_2") (pintype "passive"))
      (node (ref "T5") (pin "1") (pinfunction "G_1") (pintype "passive"))
    )
    (net (code "15") (name "/I_MOSFET1") (class "Default")
      (node (ref "T1") (pin "3") (pinfunction "S_3") (pintype "passive"))
      (node (ref "U1") (pin "4") (pinfunction "IP+_4") (pintype "passive"))
      (node (ref "U1") (pin "4_1") (pinfunction "IP+_4_1") (pintype "passive"))
      (node (ref "U1") (pin "4_10") (pinfunction "IP+_4_10") (pintype "passive"))
      (node (ref "U1") (pin "4_11") (pinfunction "IP+_4_11") (pintype "passive"))
      (node (ref "U1") (pin "4_12") (pinfunction "IP+_4_12") (pintype "passive"))
      (node (ref "U1") (pin "4_13") (pinfunction "IP+_4_13") (pintype "passive"))
      (node (ref "U1") (pin "4_14") (pinfunction "IP+_4_14") (pintype "passive"))
      (node (ref "U1") (pin "4_15") (pinfunction "IP+_4_15") (pintype "passive"))
      (node (ref "U1") (pin "4_16") (pinfunction "IP+_4_16") (pintype "passive"))
      (node (ref "U1") (pin "4_2") (pinfunction "IP+_4_2") (pintype "passive"))
      (node (ref "U1") (pin "4_3") (pinfunction "IP+_4_3") (pintype "passive"))
      (node (ref "U1") (pin "4_4") (pinfunction "IP+_4_4") (pintype "passive"))
      (node (ref "U1") (pin "4_5") (pinfunction "IP+_4_5") (pintype "passive"))
      (node (ref "U1") (pin "4_6") (pinfunction "IP+_4_6") (pintype "passive"))
      (node (ref "U1") (pin "4_7") (pinfunction "IP+_4_7") (pintype "passive"))
      (node (ref "U1") (pin "4_8") (pinfunction "IP+_4_8") (pintype "passive"))
      (node (ref "U1") (pin "4_9") (pinfunction "IP+_4_9") (pintype "passive"))
    )
    (net (code "16") (name "/I_MOSFET2") (class "Default")
      (node (ref "T5") (pin "3") (pinfunction "S_3") (pintype "passive"))
      (node (ref "U2") (pin "4") (pinfunction "IP+_4") (pintype "passive"))
      (node (ref "U2") (pin "4_1") (pinfunction "IP+_4_1") (pintype "passive"))
      (node (ref "U2") (pin "4_10") (pinfunction "IP+_4_10") (pintype "passive"))
      (node (ref "U2") (pin "4_11") (pinfunction "IP+_4_11") (pintype "passive"))
      (node (ref "U2") (pin "4_12") (pinfunction "IP+_4_12") (pintype "passive"))
      (node (ref "U2") (pin "4_13") (pinfunction "IP+_4_13") (pintype "passive"))
      (node (ref "U2") (pin "4_14") (pinfunction "IP+_4_14") (pintype "passive"))
      (node (ref "U2") (pin "4_15") (pinfunction "IP+_4_15") (pintype "passive"))
      (node (ref "U2") (pin "4_16") (pinfunction "IP+_4_16") (pintype "passive"))
      (node (ref "U2") (pin "4_2") (pinfunction "IP+_4_2") (pintype "passive"))
      (node (ref "U2") (pin "4_3") (pinfunction "IP+_4_3") (pintype "passive"))
      (node (ref "U2") (pin "4_4") (pinfunction "IP+_4_4") (pintype "passive"))
      (node (ref "U2") (pin "4_5") (pinfunction "IP+_4_5") (pintype "passive"))
      (node (ref "U2") (pin "4_6") (pinfunction "IP+_4_6") (pintype "passive"))
      (node (ref "U2") (pin "4_7") (pinfunction "IP+_4_7") (pintype "passive"))
      (node (ref "U2") (pin "4_8") (pinfunction "IP+_4_8") (pintype "passive"))
      (node (ref "U2") (pin "4_9") (pinfunction "IP+_4_9") (pintype "passive"))
    )
    (net (code "17") (name "/I_OUT1") (class "Default")
      (node (ref "R25") (pin "2") (pinfunction "2_2") (pintype "passive"))
      (node (ref "U1") (pin "3") (pinfunction "VIOUT_3") (pintype "output"))
    )
    (net (code "18") (name "/I_OUT2") (class "Default")
      (node (ref "R26") (pin "2") (pinfunction "2_2") (pintype "passive"))
      (node (ref "U2") (pin "3") (pinfunction "VIOUT_3") (pintype "output"))
    )
    (net (code "19") (name "/PWM_OUT1") (class "Default")
      (node (ref "D4") (pin "1") (pinfunction "A1_1") (pintype "passive"))
      (node (ref "D4") (pin "3") (pinfunction "A2_3") (pintype "passive"))
      (node (ref "T1") (pin "2") (pinfunction "D_2") (pintype "passive"))
      (node (ref "TRM3") (pin "1") (pinfunction "1_1") (pintype "passive"))
      (node (ref "TRM4") (pin "1") (pinfunction "1_1") (pintype "passive"))
    )
    (net (code "20") (name "/PWM_OUT2") (class "Default")
      (node (ref "D5") (pin "1") (pinfunction "A1_1") (pintype "passive"))
      (node (ref "D5") (pin "3") (pinfunction "A2_3") (pintype "passive"))
      (node (ref "T5") (pin "2") (pinfunction "D_2") (pintype "passive"))
      (node (ref "TRM7") (pin "1") (pinfunction "1_1") (pintype "passive"))
      (node (ref "TRM8") (pin "1") (pinfunction "1_1") (pintype "passive"))
    )
    (net (code "21") (name "/SW5") (class "Default")
      (node (ref "CI1") (pin "5") (pinfunction "SW_5") (pintype "passive"))
      (node (ref "CI1") (pin "9") (pinfunction "TAB_9") (pintype "passive"))
      (node (ref "D2") (pin "1") (pinfunction "K_1") (pintype "passive"))
      (node (ref "IND1") (pin "1") (pinfunction "1_1") (pintype "passive"))
    )
    (net (code "22") (name "/uC_AN1") (class "Default")
      (node (ref "CN2") (pin "7") (pinfunction "7_7") (pintype "passive"))
      (node (ref "R16") (pin "1") (pinfunction "1_1") (pintype "passive"))
    )
    (net (code "23") (name "/uC_CS1") (class "Default")
      (node (ref "CN1") (pin "8") (pinfunction "8_8") (pintype "passive"))
      (node (ref "CN5") (pin "2") (pinfunction "2_2") (pintype "passive"))
    )
    (net (code "24") (name "/uC_IN1") (class "Default")
      (node (ref "CI2") (pin "4") (pinfunction "C_4") (pintype "passive"))
      (node (ref "CN1") (pin "6") (pinfunction "6_6") (pintype "passive"))
      (node (ref "R24") (pin "1") (pinfunction "1_1") (pintype "passive"))
      (node (ref "R27") (pin "1") (pinfunction "1_1") (pintype "passive"))
    )
    (net (code "25") (name "/uC_IN2") (class "Default")
      (node (ref "CI3") (pin "4") (pinfunction "C_4") (pintype "passive"))
      (node (ref "CN1") (pin "5") (pinfunction "5_5") (pintype "passive"))
      (node (ref "R34") (pin "1") (pinfunction "1_1") (pintype "passive"))
      (node (ref "R39") (pin "1") (pinfunction "1_1") (pintype "passive"))
    )
    (net (code "26") (name "/uC_INT1") (class "Default")
      (node (ref "CN1") (pin "2") (pinfunction "2_2") (pintype "passive"))
      (node (ref "CN6") (pin "1") (pinfunction "1_1") (pintype "passive"))
    )
    (net (code "27") (name "/uC_IOUT1") (class "Default")
      (node (ref "C20") (pin "1") (pinfunction "1_1") (pintype "passive"))
      (node (ref "CN2") (pin "4") (pinfunction "4_4") (pintype "passive"))
      (node (ref "R25") (pin "1") (pinfunction "1_1") (pintype "passive"))
    )
    (net (code "28") (name "/uC_IOUT2") (class "Default")
      (node (ref "C21") (pin "1") (pinfunction "1_1") (pintype "passive"))
      (node (ref "CN2") (pin "5") (pinfunction "5_5") (pintype "passive"))
      (node (ref "R26") (pin "1") (pinfunction "1_1") (pintype "passive"))
    )
    (net (code "29") (name "/uC_NTC") (class "Default")
      (node (ref "CN2") (pin "6") (pinfunction "6_6") (pintype "passive"))
      (node (ref "R14") (pin "1") (pinfunction "1_1") (pintype "passive"))
    )
    (net (code "30") (name "/uC_PWM1") (class "Default")
      (node (ref "CN1") (pin "1") (pinfunction "1_1") (pintype "passive"))
      (node (ref "R22") (pin "1") (pinfunction "1_1") (pintype "passive"))
    )
    (net (code "31") (name "/uC_PWM2") (class "Default")
      (node (ref "CN1") (pin "3") (pinfunction "3_3") (pintype "passive"))
      (node (ref "R36") (pin "1") (pinfunction "1_1") (pintype "passive"))
    )
    (net (code "32") (name "/uC_SCK1") (class "Default")
      (node (ref "CN3") (pin "3") (pinfunction "3_3") (pintype "passive"))
      (node (ref "CN5") (pin "3") (pinfunction "3_3") (pintype "passive"))
    )
    (net (code "33") (name "/uC_SI1") (class "Default")
      (node (ref "CN3") (pin "6") (pinfunction "6_6") (pintype "passive"))
      (node (ref "CN5") (pin "4") (pinfunction "4_4") (pintype "passive"))
    )
    (net (code "34") (name "/uC_SO1") (class "Default")
      (node (ref "CN3") (pin "5") (pinfunction "5_5") (pintype "passive"))
      (node (ref "CN6") (pin "2") (pinfunction "2_2") (pintype "passive"))
    )
    (net (code "35") (name "/uC_VMap") (class "Default")
      (node (ref "C15") (pin "1") (pinfunction "1_1") (pintype "passive"))
      (node (ref "CN2") (pin "3") (pinfunction "3_3") (pintype "passive"))
      (node (ref "R11") (pin "1") (pinfunction "1_1") (pintype "passive"))
    )
    (net (code "36") (name "/uC_Vin") (class "Default")
      (node (ref "CN2") (pin "2") (pinfunction "2_2") (pintype "passive"))
      (node (ref "R4") (pin "1") (pinfunction "1_1") (pintype "passive"))
      (node (ref "R6") (pin "2") (pinfunction "2_2") (pintype "passive"))
    )
    (net (code "37") (name "GND") (class "Default")
      (node (ref "B1") (pin "2") (pinfunction "GROUND_2") (pintype "passive"))
      (node (ref "C1") (pin "2") (pinfunction "2_2") (pintype "passive"))
      (node (ref "C10") (pin "1") (pinfunction "Minus_1") (pintype "passive"))
      (node (ref "C11") (pin "2") (pinfunction "2_2") (pintype "passive"))
      (node (ref "C12") (pin "1") (pinfunction "1_1") (pintype "passive"))
      (node (ref "C13") (pin "1") (pinfunction "1_1") (pintype "passive"))
      (node (ref "C14") (pin "2") (pinfunction "2_2") (pintype "passive"))
      (node (ref "C15") (pin "2") (pinfunction "2_2") (pintype "passive"))
      (node (ref "C16") (pin "2") (pinfunction "2_2") (pintype "passive"))
      (node (ref "C17") (pin "2") (pinfunction "2_2") (pintype "passive"))
      (node (ref "C18") (pin "2") (pinfunction "2_2") (pintype "passive"))
      (node (ref "C19") (pin "2") (pinfunction "2_2") (pintype "passive"))
      (node (ref "C20") (pin "2") (pinfunction "2_2") (pintype "passive"))
      (node (ref "C21") (pin "2") (pinfunction "2_2") (pintype "passive"))
      (node (ref "C3") (pin "2") (pinfunction "2_2") (pintype "passive"))
      (node (ref "C4") (pin "1") (pinfunction "Minus_1") (pintype "passive"))
      (node (ref "C5") (pin "1") (pinfunction "Minus_1") (pintype "passive"))
      (node (ref "C6") (pin "1") (pinfunction "Minus_1") (pintype "passive"))
      (node (ref "C7") (pin "1") (pinfunction "Minus_1") (pintype "passive"))
      (node (ref "C8") (pin "2") (pinfunction "2_2") (pintype "passive"))
      (node (ref "CI1") (pin "6") (pinfunction "EN_6") (pintype "passive"))
      (node (ref "CI1") (pin "7") (pinfunction "GND_7") (pintype "passive"))
      (node (ref "CI2") (pin "3") (pinfunction "E_3") (pintype "passive"))
      (node (ref "CI3") (pin "3") (pinfunction "E_3") (pintype "passive"))
      (node (ref "CN2") (pin "9") (pinfunction "9_9") (pintype "passive"))
      (node (ref "CN3") (pin "4") (pinfunction "4_4") (pintype "passive"))
      (node (ref "CN6") (pin "3") (pinfunction "3_3") (pintype "passive"))
      (node (ref "D2") (pin "2") (pinfunction "A_2") (pintype "passive"))
      (node (ref "D3") (pin "3") (pinfunction "3_3") (pintype "passive"))
      (node (ref "J1") (pin "10") (pinfunction "10_10") (pintype "passive"))
      (node (ref "J1") (pin "2") (pinfunction "2_2") (pintype "passive"))
      (node (ref "NTC1") (pin "1") (pinfunction "1_1") (pintype "passive"))
      (node (ref "NTC2") (pin "1") (pinfunction "1_1") (pintype "passive"))
      (node (ref "R17") (pin "2") (pinfunction "2_2") (pintype "passive"))
      (node (ref "R23") (pin "1") (pinfunction "1_1") (pintype "passive"))
      (node (ref "R29") (pin "1") (pinfunction "1_1") (pintype "passive"))
      (node (ref "R37") (pin "1") (pinfunction "1_1") (pintype "passive"))
      (node (ref "R38") (pin "1") (pinfunction "1_1") (pintype "passive"))
      (node (ref "R6") (pin "1") (pinfunction "1_1") (pintype "passive"))
      (node (ref "R8") (pin "1") (pinfunction "1_1") (pintype "passive"))
      (node (ref "T3") (pin "3") (pinfunction "C_3") (pintype "passive"))
      (node (ref "T4") (pin "2") (pinfunction "E_2") (pintype "passive"))
      (node (ref "T7") (pin "3") (pinfunction "C_3") (pintype "passive"))
      (node (ref "T8") (pin "2") (pinfunction "E_2") (pintype "passive"))
      (node (ref "U1") (pin "2") (pinfunction "GND_2") (pintype "power_in"))
      (node (ref "U2") (pin "2") (pinfunction "GND_2") (pintype "power_in"))
    )
    (net (code "38") (name "Net-(B1-VOUT)") (class "Default")
      (node (ref "B1") (pin "1") (pinfunction "VOUT_1") (pintype "passive"))
      (node (ref "R11") (pin "2") (pinfunction "2_2") (pintype "passive"))
    )
    (net (code "39") (name "Net-(C11-Pad1)") (class "Default")
      (node (ref "C11") (pin "1") (pinfunction "1_1") (pintype "passive"))
      (node (ref "CN2") (pin "1") (pinfunction "1_1") (pintype "passive"))
      (node (ref "R2") (pin "1") (pinfunction "1_1") (pintype "passive"))
    )
    (net (code "40") (name "Net-(C16-Pad1)") (class "Default")
      (node (ref "C16") (pin "1") (pinfunction "1_1") (pintype "passive"))
      (node (ref "NTC1") (pin "2") (pinfunction "2_2") (pintype "passive"))
      (node (ref "NTC2") (pin "2") (pinfunction "2_2") (pintype "passive"))
      (node (ref "R13") (pin "1") (pinfunction "1_1") (pintype "passive"))
      (node (ref "R14") (pin "2") (pinfunction "2_2") (pintype "passive"))
    )
    (net (code "41") (name "Net-(CI1-VC)") (class "Default")
      (node (ref "C2") (pin "2") (pinfunction "2_2") (pintype "passive"))
      (node (ref "CI1") (pin "3") (pinfunction "VC_3") (pintype "passive"))
    )
    (net (code "42") (name "Net-(CN4-Pad1)") (class "Default")
      (node (ref "CN4") (pin "1") (pinfunction "1_1") (pintype "passive"))
      (node (ref "R9") (pin "2") (pinfunction "2_2") (pintype "passive"))
    )
    (net (code "43") (name "Net-(CN4-Pad2)") (class "Default")
      (node (ref "CN4") (pin "2") (pinfunction "2_2") (pintype "passive"))
      (node (ref "R10") (pin "2") (pinfunction "2_2") (pintype "passive"))
    )
    (net (code "44") (name "Net-(D3-Pad1)") (class "Default")
      (node (ref "D3") (pin "1") (pinfunction "1_1") (pintype "passive"))
      (node (ref "PTC1") (pin "2") (pinfunction "2_2") (pintype "passive"))
      (node (ref "R9") (pin "1") (pinfunction "1_1") (pintype "passive"))
    )
    (net (code "45") (name "Net-(D3-Pad2)") (class "Default")
      (node (ref "D3") (pin "2") (pinfunction "2_2") (pintype "passive"))
      (node (ref "PTC2") (pin "2") (pinfunction "2_2") (pintype "passive"))
      (node (ref "R10") (pin "1") (pinfunction "1_1") (pintype "passive"))
    )
    (net (code "46") (name "Net-(R3-Pad1)") (class "Default")
      (node (ref "R3") (pin "1") (pinfunction "1_1") (pintype "passive"))
      (node (ref "R5") (pin "2") (pinfunction "2_2") (pintype "passive"))
    )
    (net (code "47") (name "Net-(R5-Pad1)") (class "Default")
      (node (ref "R5") (pin "1") (pinfunction "1_1") (pintype "passive"))
      (node (ref "R7") (pin "2") (pinfunction "2_2") (pintype "passive"))
    )
    (net (code "48") (name "Net-(T2-B)") (class "Default")
      (node (ref "R18") (pin "1") (pinfunction "1_1") (pintype "passive"))
      (node (ref "R21") (pin "2") (pinfunction "2_2") (pintype "passive"))
      (node (ref "T2") (pin "1") (pinfunction "B_1") (pintype "passive"))
      (node (ref "T3") (pin "1") (pinfunction "B_1") (pintype "passive"))
    )
    (net (code "49") (name "Net-(T2-E)") (class "Default")
      (node (ref "R19") (pin "1") (pinfunction "1_1") (pintype "passive"))
      (node (ref "T2") (pin "2") (pinfunction "E_2") (pintype "passive"))
      (node (ref "T3") (pin "2") (pinfunction "E_2") (pintype "passive"))
    )
    (net (code "50") (name "Net-(T4-B)") (class "Default")
      (node (ref "R20") (pin "1") (pinfunction "1_1") (pintype "passive"))
      (node (ref "R22") (pin "2") (pinfunction "2_2") (pintype "passive"))
      (node (ref "R24") (pin "2") (pinfunction "2_2") (pintype "passive"))
      (node (ref "T4") (pin "1") (pinfunction "B_1") (pintype "passive"))
    )
    (net (code "51") (name "Net-(T4-C)") (class "Default")
      (node (ref "R21") (pin "1") (pinfunction "1_1") (pintype "passive"))
      (node (ref "T4") (pin "3") (pinfunction "C_3") (pintype "passive"))
    )
    (net (code "52") (name "Net-(T6-B)") (class "Default")
      (node (ref "R30") (pin "1") (pinfunction "1_1") (pintype "passive"))
      (node (ref "R33") (pin "2") (pinfunction "2_2") (pintype "passive"))
      (node (ref "T6") (pin "1") (pinfunction "B_1") (pintype "passive"))
      (node (ref "T7") (pin "1") (pinfunction "B_1") (pintype "passive"))
    )
    (net (code "53") (name "Net-(T6-E)") (class "Default")
      (node (ref "R31") (pin "1") (pinfunction "1_1") (pintype "passive"))
      (node (ref "T6") (pin "2") (pinfunction "E_2") (pintype "passive"))
      (node (ref "T7") (pin "2") (pinfunction "E_2") (pintype "passive"))
    )
    (net (code "54") (name "Net-(T8-B)") (class "Default")
      (node (ref "R32") (pin "1") (pinfunction "1_1") (pintype "passive"))
      (node (ref "R36") (pin "2") (pinfunction "2_2") (pintype "passive"))
      (node (ref "R39") (pin "2") (pinfunction "2_2") (pintype "passive"))
      (node (ref "T8") (pin "1") (pinfunction "B_1") (pintype "passive"))
    )
    (net (code "55") (name "Net-(T8-C)") (class "Default")
      (node (ref "R33") (pin "1") (pinfunction "1_1") (pintype "passive"))
      (node (ref "T8") (pin "3") (pinfunction "C_3") (pintype "passive"))
    )
    (net (code "56") (name "VCC") (class "Default")
      (node (ref "D1") (pin "2") (pinfunction "A_2") (pintype "passive"))
      (node (ref "J1") (pin "1") (pinfunction "1_1") (pintype "passive"))
      (node (ref "J1") (pin "9") (pinfunction "9_9") (pintype "passive"))
    )
    (net (code "57") (name "VCC1") (class "Default")
      (node (ref "D4") (pin "2") (pinfunction "K_2") (pintype "passive"))
      (node (ref "TRM1") (pin "1") (pinfunction "1_1") (pintype "passive"))
      (node (ref "TRM2") (pin "1") (pinfunction "1_1") (pintype "passive"))
    )
    (net (code "58") (name "VCC2") (class "Default")
      (node (ref "D5") (pin "2") (pinfunction "K_2") (pintype "passive"))
      (node (ref "TRM5") (pin "1") (pinfunction "1_1") (pintype "passive"))
      (node (ref "TRM6") (pin "1") (pinfunction "1_1") (pintype "passive"))
    )
    (net (code "59") (name "power_GND1") (class "Default")
      (node (ref "TRM11") (pin "1") (pinfunction "1_1") (pintype "passive"))
      (node (ref "TRM9") (pin "1") (pinfunction "1_1") (pintype "passive"))
      (node (ref "U1") (pin "5") (pinfunction "IP-_5") (pintype "passive"))
      (node (ref "U1") (pin "5_1") (pinfunction "IP-_5_1") (pintype "passive"))
      (node (ref "U1") (pin "5_10") (pinfunction "IP-_5_10") (pintype "passive"))
      (node (ref "U1") (pin "5_11") (pinfunction "IP-_5_11") (pintype "passive"))
      (node (ref "U1") (pin "5_12") (pinfunction "IP-_5_12") (pintype "passive"))
      (node (ref "U1") (pin "5_13") (pinfunction "IP-_5_13") (pintype "passive"))
      (node (ref "U1") (pin "5_14") (pinfunction "IP-_5_14") (pintype "passive"))
      (node (ref "U1") (pin "5_15") (pinfunction "IP-_5_15") (pintype "passive"))
      (node (ref "U1") (pin "5_16") (pinfunction "IP-_5_16") (pintype "passive"))
      (node (ref "U1") (pin "5_2") (pinfunction "IP-_5_2") (pintype "passive"))
      (node (ref "U1") (pin "5_3") (pinfunction "IP-_5_3") (pintype "passive"))
      (node (ref "U1") (pin "5_4") (pinfunction "IP-_5_4") (pintype "passive"))
      (node (ref "U1") (pin "5_5") (pinfunction "IP-_5_5") (pintype "passive"))
      (node (ref "U1") (pin "5_6") (pinfunction "IP-_5_6") (pintype "passive"))
      (node (ref "U1") (pin "5_7") (pinfunction "IP-_5_7") (pintype "passive"))
      (node (ref "U1") (pin "5_8") (pinfunction "IP-_5_8") (pintype "passive"))
      (node (ref "U1") (pin "5_9") (pinfunction "IP-_5_9") (pintype "passive"))
    )
    (net (code "60") (name "power_GND2") (class "Default")
      (node (ref "TRM10") (pin "1") (pinfunction "1_1") (pintype "passive"))
      (node (ref "TRM12") (pin "1") (pinfunction "1_1") (pintype "passive"))
      (node (ref "U2") (pin "5") (pinfunction "IP-_5") (pintype "passive"))
      (node (ref "U2") (pin "5_1") (pinfunction "IP-_5_1") (pintype "passive"))
      (node (ref "U2") (pin "5_10") (pinfunction "IP-_5_10") (pintype "passive"))
      (node (ref "U2") (pin "5_11") (pinfunction "IP-_5_11") (pintype "passive"))
      (node (ref "U2") (pin "5_12") (pinfunction "IP-_5_12") (pintype "passive"))
      (node (ref "U2") (pin "5_13") (pinfunction "IP-_5_13") (pintype "passive"))
      (node (ref "U2") (pin "5_14") (pinfunction "IP-_5_14") (pintype "passive"))
      (node (ref "U2") (pin "5_15") (pinfunction "IP-_5_15") (pintype "passive"))
      (node (ref "U2") (pin "5_16") (pinfunction "IP-_5_16") (pintype "passive"))
      (node (ref "U2") (pin "5_2") (pinfunction "IP-_5_2") (pintype "passive"))
      (node (ref "U2") (pin "5_3") (pinfunction "IP-_5_3") (pintype "passive"))
      (node (ref "U2") (pin "5_4") (pinfunction "IP-_5_4") (pintype "passive"))
      (node (ref "U2") (pin "5_5") (pinfunction "IP-_5_5") (pintype "passive"))
      (node (ref "U2") (pin "5_6") (pinfunction "IP-_5_6") (pintype "passive"))
      (node (ref "U2") (pin "5_7") (pinfunction "IP-_5_7") (pintype "passive"))
      (node (ref "U2") (pin "5_8") (pinfunction "IP-_5_8") (pintype "passive"))
      (node (ref "U2") (pin "5_9") (pinfunction "IP-_5_9") (pintype "passive"))
    )
    (net (code "61") (name "unconnected-(B1-V1-Pad4)") (class "Default")
      (node (ref "B1") (pin "4") (pinfunction "V1_4") (pintype "passive+no_connect"))
    )
    (net (code "62") (name "unconnected-(B1-V2-Pad5)") (class "Default")
      (node (ref "B1") (pin "5") (pinfunction "V2_5") (pintype "passive+no_connect"))
    )
    (net (code "63") (name "unconnected-(B1-VEX-Pad6)") (class "Default")
      (node (ref "B1") (pin "6") (pinfunction "VEX_6") (pintype "passive"))
    )
    (net (code "64") (name "unconnected-(CN1-Pad4)") (class "Default")
      (node (ref "CN1") (pin "4") (pinfunction "4_4") (pintype "passive"))
    )
    (net (code "65") (name "unconnected-(CN1-Pad7)") (class "Default")
      (node (ref "CN1") (pin "7") (pinfunction "7_7") (pintype "passive"))
    )
    (net (code "66") (name "unconnected-(CN3-Pad1)") (class "Default")
      (node (ref "CN3") (pin "1") (pinfunction "1_1") (pintype "passive"))
    )
    (net (code "67") (name "unconnected-(CN3-Pad2)") (class "Default")
      (node (ref "CN3") (pin "2") (pinfunction "2_2") (pintype "passive"))
    )
    (net (code "68") (name "unconnected-(J1-Pad3)") (class "Default")
      (node (ref "J1") (pin "3") (pinfunction "3_3") (pintype "passive+no_connect"))
    )
    (net (code "69") (name "unconnected-(J1-Pad4)") (class "Default")
      (node (ref "J1") (pin "4") (pinfunction "4_4") (pintype "passive+no_connect"))
    )
    (net (code "70") (name "unconnected-(J1-Pad7)") (class "Default")
      (node (ref "J1") (pin "7") (pinfunction "7_7") (pintype "passive+no_connect"))
    )
    (net (code "71") (name "unconnected-(J1-Pad11)") (class "Default")
      (node (ref "J1") (pin "11") (pinfunction "11_11") (pintype "passive+no_connect"))
    )
    (net (code "72") (name "unconnected-(J1-Pad12)") (class "Default")
      (node (ref "J1") (pin "12") (pinfunction "12_12") (pintype "passive+no_connect"))
    )
  )
)
